# Carrier_Cancellation_Circuit.net
KiCad netlist of a schematic drawn in Altium Designer
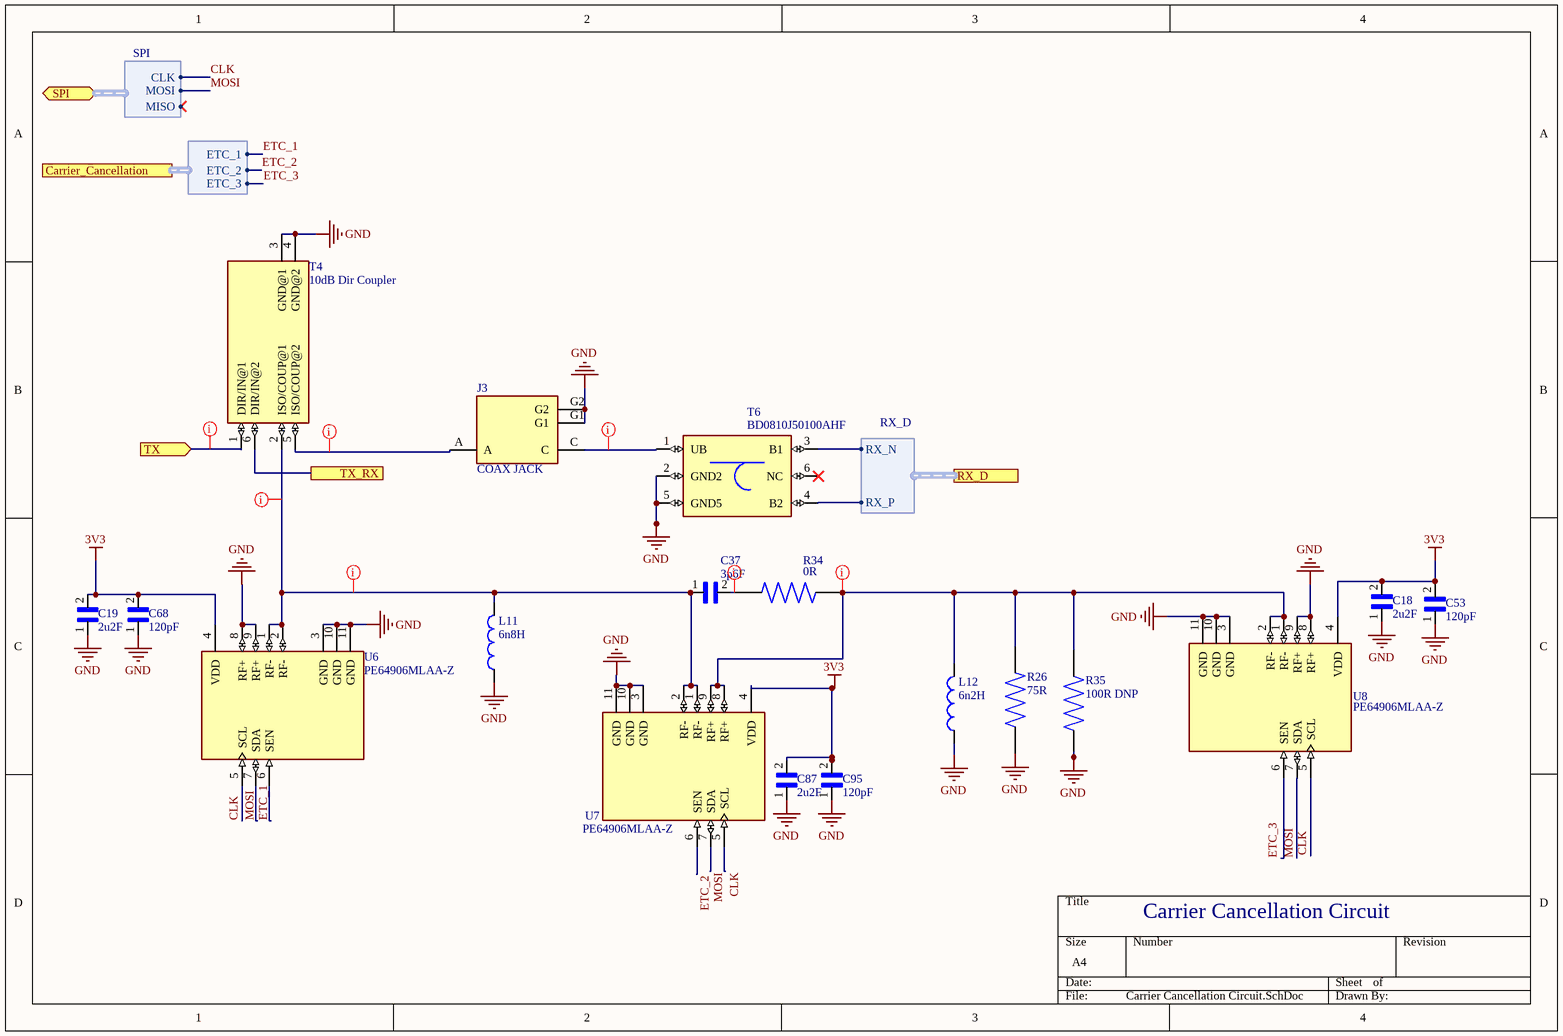
[diagram p0: Carrier Cancellation Circuit.SchDoc]

(export (version "E")
  (design (tool "Eeschema 10.0.6"))
  (components
    (comp (ref "C18")
      (value "2u2F")
      (footprint "CAPC0603X35N")
      (description "SMD Capacitor X5R(EIA) with Capacitance: 2.2uF Tol. 20%. Rated Voltage: 6.3Vdc")
      (fields (field (name "MP") "GRM033R60J225ME15D"))
      (libsource (lib "GRM033R60J225ME15D") (part "GRM033R60J225ME15D"))
    )
    (comp (ref "C19")
      (value "2u2F")
      (footprint "CAPC0603X35N")
      (description "SMD Capacitor X5R(EIA) with Capacitance: 2.2uF Tol. 20%. Rated Voltage: 6.3Vdc")
      (fields (field (name "MP") "GRM033R60J225ME15D"))
      (libsource (lib "GRM033R60J225ME15D") (part "GRM033R60J225ME15D"))
    )
    (comp (ref "C37")
      (value "3p6F")
      (footprint "CAPC1005X55N")
      (description "SMD Capacitor C0G(EIA) with Capacitance: 3.6pF Tol. 0.1pF. Rated Voltage: 50Vdc")
      (fields (field (name "MP") "GRM1555C1H3R6BA01D") (field (name "MF") "Murata Electronics"))
      (libsource (lib "GRM1555C1H3R6BA01D") (part "GRM1555C1H3R6BA01D"))
    )
    (comp (ref "C53")
      (value "120pF")
      (footprint "CAPC0603X33N")
      (description "0201 120 pF 50 V Â±5% Tolerance C0G SMT Multilayer Ceramic Capacitor")
      (fields (field (name "MF") "Murata Electronics") (field (name "MP") "GRM0335C1H121JA01D"))
      (libsource (lib "GRM0335C1H121JA01D") (part "GRM0335C1H121JA01D"))
    )
    (comp (ref "C68")
      (value "120pF")
      (footprint "CAPC0603X33N")
      (description "0201 120 pF 50 V Â±5% Tolerance C0G SMT Multilayer Ceramic Capacitor")
      (fields (field (name "MF") "Murata Electronics") (field (name "MP") "GRM0335C1H121JA01D"))
      (libsource (lib "GRM0335C1H121JA01D") (part "GRM0335C1H121JA01D"))
    )
    (comp (ref "C87")
      (value "2u2F")
      (footprint "CAPC0603X35N")
      (description "SMD Capacitor X5R(EIA) with Capacitance: 2.2uF Tol. 20%. Rated Voltage: 6.3Vdc")
      (fields (field (name "MP") "GRM033R60J225ME15D"))
      (libsource (lib "GRM033R60J225ME15D") (part "GRM033R60J225ME15D"))
    )
    (comp (ref "C95")
      (value "120pF")
      (footprint "CAPC0603X33N")
      (description "0201 120 pF 50 V Â±5% Tolerance C0G SMT Multilayer Ceramic Capacitor")
      (fields (field (name "MF") "Murata Electronics") (field (name "MP") "GRM0335C1H121JA01D"))
      (libsource (lib "GRM0335C1H121JA01D") (part "GRM0335C1H121JA01D"))
    )
    (comp (ref "J3")
      (value "COAX JACK")
      (footprint "SW_MS-156HF(01)")
      (description "Coaxial Switch - 4mm Plug Dia Connector Receptacle, Female Socket 50Ohm Surface Mount Solder")
      (fields (field (name "MP") "MS-156HF(01)") (field (name "MF") "Hirose Electric"))
      (libsource (lib "MS-156HF_01_") (part "MS-156HF(01)"))
    )
    (comp (ref "L11")
      (value "6n8H")
      (footprint "INDC1006X60N")
      (description "Inductor with Inductance: 6.8nH Tol. +/-2%, Package: 0402 (1005)")
      (fields (field (name "MP") "LQW15AN6N8G00D") (field (name "MF") "Murata"))
      (libsource (lib "LQW15AN6N8G00D") (part "LQW15AN6N8G00D"))
    )
    (comp (ref "L12")
      (value "6n2H")
      (footprint "INDC1006X60N")
      (description "Ind RF Chip Wirewound 5.6nH 0.2nH 100MHz 30Q-Factor 800mA 0402 Paper T/R")
      (fields (field (name "MP") "LQW15AN5N6C10D"))
      (libsource (lib "LQW15AN5N6C10D") (part "LQW15AN5N6C10D"))
    )
    (comp (ref "R26")
      (value "75R")
      (footprint "RES_ERJ2RKF75R0X")
      (fields (field (name "MP") "ERJ2RKF75R0X"))
      (libsource (lib "ERJ2RKF75R0X") (part "ERJ2RKF75R0X"))
    )
    (comp (ref "R34")
      (value "0R")
      (footprint "RESC1005X37N")
      (fields (field (name "MF") "{'manufacturer': u'YAGEO'}") (field (name "MP") "RC0402JR-070RL"))
      (libsource (lib "RC0402JR-070RL") (part "RC0402JR-070RL"))
    )
    (comp (ref "R35")
      (value "100R DNP")
      (footprint "RES_ERJ2RKF75R0X")
      (fields (field (name "MP") "ERJ2RKF75R0X"))
      (libsource (lib "ERJ2RKF75R0X") (part "ERJ2RKF75R0X"))
    )
    (comp (ref "T4")
      (value "10dB Dir Coupler")
      (footprint "PSON65P164X204X84-6N")
      (description "RF Directional Coupler General Purpose 700MHz ~ 1GHz 10.9dB 2W 0805 (2012 Metric)")
      (fields (field (name "MF") "Anaren") (field (name "MP") "DC0710J5010AHF"))
      (libsource (lib "DC0710J5010AHF") (part "DC0710J5010AHF"))
    )
    (comp (ref "T6")
      (value "BD0810J50100AHF")
      (footprint "BD0810J50100AHF")
      (description "Signal Conditioning 800-1000MHz 50/100 Ohm IL=.95dB")
      (fields (field (name "MF") "ttm technologies"))
      (libsource (lib "BD0810J50100AHF") (part "BD0810J50100AHF"))
    )
    (comp (ref "U6")
      (value "PE64906MLAA-Z")
      (footprint "QFN50P200X200X60-11N")
      (description "Murata Digitally Tunable Capacitor (100-3000 MHz) 0.9-4.6pF, SPI Interface")
      (fields (field (name "MF") "pSemi"))
      (libsource (lib "PE64906MLAA-Z") (part "PE64906MLAA-Z"))
    )
    (comp (ref "U7")
      (value "PE64906MLAA-Z")
      (footprint "QFN50P200X200X60-11N")
      (description "Murata Digitally Tunable Capacitor (100-3000 MHz) 0.9-4.6pF, SPI Interface")
      (fields (field (name "MF") "pSemi"))
      (libsource (lib "") (part "PE64906MLAA-Z_1"))
    )
    (comp (ref "U8")
      (value "PE64906MLAA-Z")
      (footprint "QFN50P200X200X60-11N")
      (description "Murata Digitally Tunable Capacitor (100-3000 MHz) 0.9-4.6pF, SPI Interface")
      (fields (field (name "MF") "pSemi"))
      (libsource (lib "") (part "PE64906MLAA-Z_1"))
    )
  )
  (nets
    (net (code "4") (name "/CLK") (class "Default")
      (node (ref "U6") (pin "5") (pinfunction "SCL_5") (pintype "input"))
      (node (ref "U7") (pin "5") (pinfunction "SCL_5") (pintype "input"))
      (node (ref "U8") (pin "5") (pinfunction "SCL_5") (pintype "input"))
    )
    (net (code "5") (name "/ETC_1") (class "Default")
      (node (ref "U6") (pin "6") (pinfunction "SEN_6") (pintype "input"))
    )
    (net (code "6") (name "/ETC_2") (class "Default")
      (node (ref "U7") (pin "6") (pinfunction "SEN_6") (pintype "input"))
    )
    (net (code "7") (name "/ETC_3") (class "Default")
      (node (ref "U8") (pin "6") (pinfunction "SEN_6") (pintype "input"))
    )
    (net (code "8") (name "/MOSI") (class "Default")
      (node (ref "U6") (pin "7") (pinfunction "SDA_7") (pintype "bidirectional"))
      (node (ref "U7") (pin "7") (pinfunction "SDA_7") (pintype "bidirectional"))
      (node (ref "U8") (pin "7") (pinfunction "SDA_7") (pintype "bidirectional"))
    )
    (net (code "9") (name "/RX_N") (class "Default")
      (node (ref "T6") (pin "3") (pinfunction "B1_3") (pintype "bidirectional"))
    )
    (net (code "10") (name "/RX_P") (class "Default")
      (node (ref "T6") (pin "4") (pinfunction "B2_4") (pintype "bidirectional"))
    )
    (net (code "11") (name "/TX") (class "Default")
      (node (ref "T4") (pin "1") (pinfunction "DIR/IN@1_1") (pintype "bidirectional"))
    )
    (net (code "12") (name "/TX_RX") (class "Default")
      (node (ref "T4") (pin "6") (pinfunction "DIR/IN@2_6") (pintype "bidirectional"))
    )
    (net (code "16") (name "3V3") (class "Default")
      (node (ref "C18") (pin "2") (pinfunction "2_2") (pintype "passive"))
      (node (ref "C19") (pin "2") (pinfunction "2_2") (pintype "passive"))
      (node (ref "C53") (pin "2") (pinfunction "2_2") (pintype "passive"))
      (node (ref "C68") (pin "2") (pinfunction "2_2") (pintype "passive"))
      (node (ref "C87") (pin "2") (pinfunction "2_2") (pintype "passive"))
      (node (ref "C95") (pin "2") (pinfunction "2_2") (pintype "passive"))
      (node (ref "U6") (pin "4") (pinfunction "VDD_4") (pintype "power_in"))
      (node (ref "U7") (pin "4") (pinfunction "VDD_4") (pintype "power_in"))
      (node (ref "U8") (pin "4") (pinfunction "VDD_4") (pintype "power_in"))
    )
    (net (code "17") (name "GND") (class "Default")
      (node (ref "C18") (pin "1") (pinfunction "1_1") (pintype "passive"))
      (node (ref "C19") (pin "1") (pinfunction "1_1") (pintype "passive"))
      (node (ref "C53") (pin "1") (pinfunction "1_1") (pintype "passive"))
      (node (ref "C68") (pin "1") (pinfunction "1_1") (pintype "passive"))
      (node (ref "C87") (pin "1") (pinfunction "1_1") (pintype "passive"))
      (node (ref "C95") (pin "1") (pinfunction "1_1") (pintype "passive"))
      (node (ref "J3") (pin "G1") (pinfunction "G1_G1") (pintype "power_in"))
      (node (ref "J3") (pin "G2") (pinfunction "G2_G2") (pintype "power_in"))
      (node (ref "L11") (pin "1") (pinfunction "1_1") (pintype "passive"))
      (node (ref "L12") (pin "1") (pinfunction "1_1") (pintype "passive"))
      (node (ref "R26") (pin "1") (pinfunction "1_1") (pintype "passive"))
      (node (ref "R35") (pin "1") (pinfunction "1_1") (pintype "passive"))
      (node (ref "T4") (pin "3") (pinfunction "GND@1_3") (pintype "power_in"))
      (node (ref "T4") (pin "4") (pinfunction "GND@2_4") (pintype "power_in"))
      (node (ref "T6") (pin "2") (pinfunction "GND2_2") (pintype "bidirectional"))
      (node (ref "T6") (pin "5") (pinfunction "GND5_5") (pintype "bidirectional"))
      (node (ref "U6") (pin "10") (pinfunction "GND_10") (pintype "power_in"))
      (node (ref "U6") (pin "11") (pinfunction "GND_11") (pintype "power_in"))
      (node (ref "U6") (pin "3") (pinfunction "GND_3") (pintype "power_in"))
      (node (ref "U6") (pin "8") (pinfunction "RF+_8") (pintype "bidirectional"))
      (node (ref "U6") (pin "9") (pinfunction "RF+_9") (pintype "bidirectional"))
      (node (ref "U7") (pin "10") (pinfunction "GND_10") (pintype "power_in"))
      (node (ref "U7") (pin "11") (pinfunction "GND_11") (pintype "power_in"))
      (node (ref "U7") (pin "3") (pinfunction "GND_3") (pintype "power_in"))
      (node (ref "U8") (pin "10") (pinfunction "GND_10") (pintype "power_in"))
      (node (ref "U8") (pin "11") (pinfunction "GND_11") (pintype "power_in"))
      (node (ref "U8") (pin "3") (pinfunction "GND_3") (pintype "power_in"))
      (node (ref "U8") (pin "8") (pinfunction "RF+_8") (pintype "bidirectional"))
      (node (ref "U8") (pin "9") (pinfunction "RF+_9") (pintype "bidirectional"))
    )
    (net (code "18") (name "Net-(C37-Pad2)") (class "Default")
      (node (ref "C37") (pin "2") (pinfunction "2_2") (pintype "passive"))
      (node (ref "R34") (pin "1") (pinfunction "1_1") (pintype "passive"))
    )
    (net (code "19") (name "Net-(L12-Pad2)") (class "Default")
      (node (ref "L12") (pin "2") (pinfunction "2_2") (pintype "passive"))
      (node (ref "R26") (pin "2") (pinfunction "2_2") (pintype "passive"))
      (node (ref "R34") (pin "2") (pinfunction "2_2") (pintype "passive"))
      (node (ref "R35") (pin "2") (pinfunction "2_2") (pintype "passive"))
      (node (ref "U7") (pin "8") (pinfunction "RF+_8") (pintype "bidirectional"))
      (node (ref "U7") (pin "9") (pinfunction "RF+_9") (pintype "bidirectional"))
      (node (ref "U8") (pin "1") (pinfunction "RF-_1") (pintype "bidirectional"))
      (node (ref "U8") (pin "2") (pinfunction "RF-_2") (pintype "bidirectional"))
    )
    (net (code "20") (name "Net-(T4-ISO{slash}COUP@1)") (class "Default")
      (node (ref "C37") (pin "1") (pinfunction "1_1") (pintype "passive"))
      (node (ref "L11") (pin "2") (pinfunction "2_2") (pintype "passive"))
      (node (ref "T4") (pin "2") (pinfunction "ISO/COUP@1_2") (pintype "bidirectional"))
      (node (ref "U6") (pin "1") (pinfunction "RF-_1") (pintype "bidirectional"))
      (node (ref "U6") (pin "2") (pinfunction "RF-_2") (pintype "bidirectional"))
      (node (ref "U7") (pin "1") (pinfunction "RF-_1") (pintype "bidirectional"))
      (node (ref "U7") (pin "2") (pinfunction "RF-_2") (pintype "bidirectional"))
    )
    (net (code "21") (name "Net-(T4-ISO{slash}COUP@2)") (class "Default")
      (node (ref "J3") (pin "A") (pinfunction "A_A") (pintype "passive"))
      (node (ref "T4") (pin "5") (pinfunction "ISO/COUP@2_5") (pintype "bidirectional"))
    )
    (net (code "22") (name "Net-(T6-UB)") (class "Default")
      (node (ref "J3") (pin "C") (pinfunction "C_C") (pintype "passive"))
      (node (ref "T6") (pin "1") (pinfunction "UB_1") (pintype "bidirectional"))
    )
    (net (code "23") (name "unconnected-(T6-NC-Pad6)") (class "Default")
      (node (ref "T6") (pin "6") (pinfunction "NC_6") (pintype "bidirectional+no_connect"))
    )
  )
)
